# Steering_Wheel_Interface_Digital_Inputs.net
KiCad netlist of a schematic drawn in Altium Designer
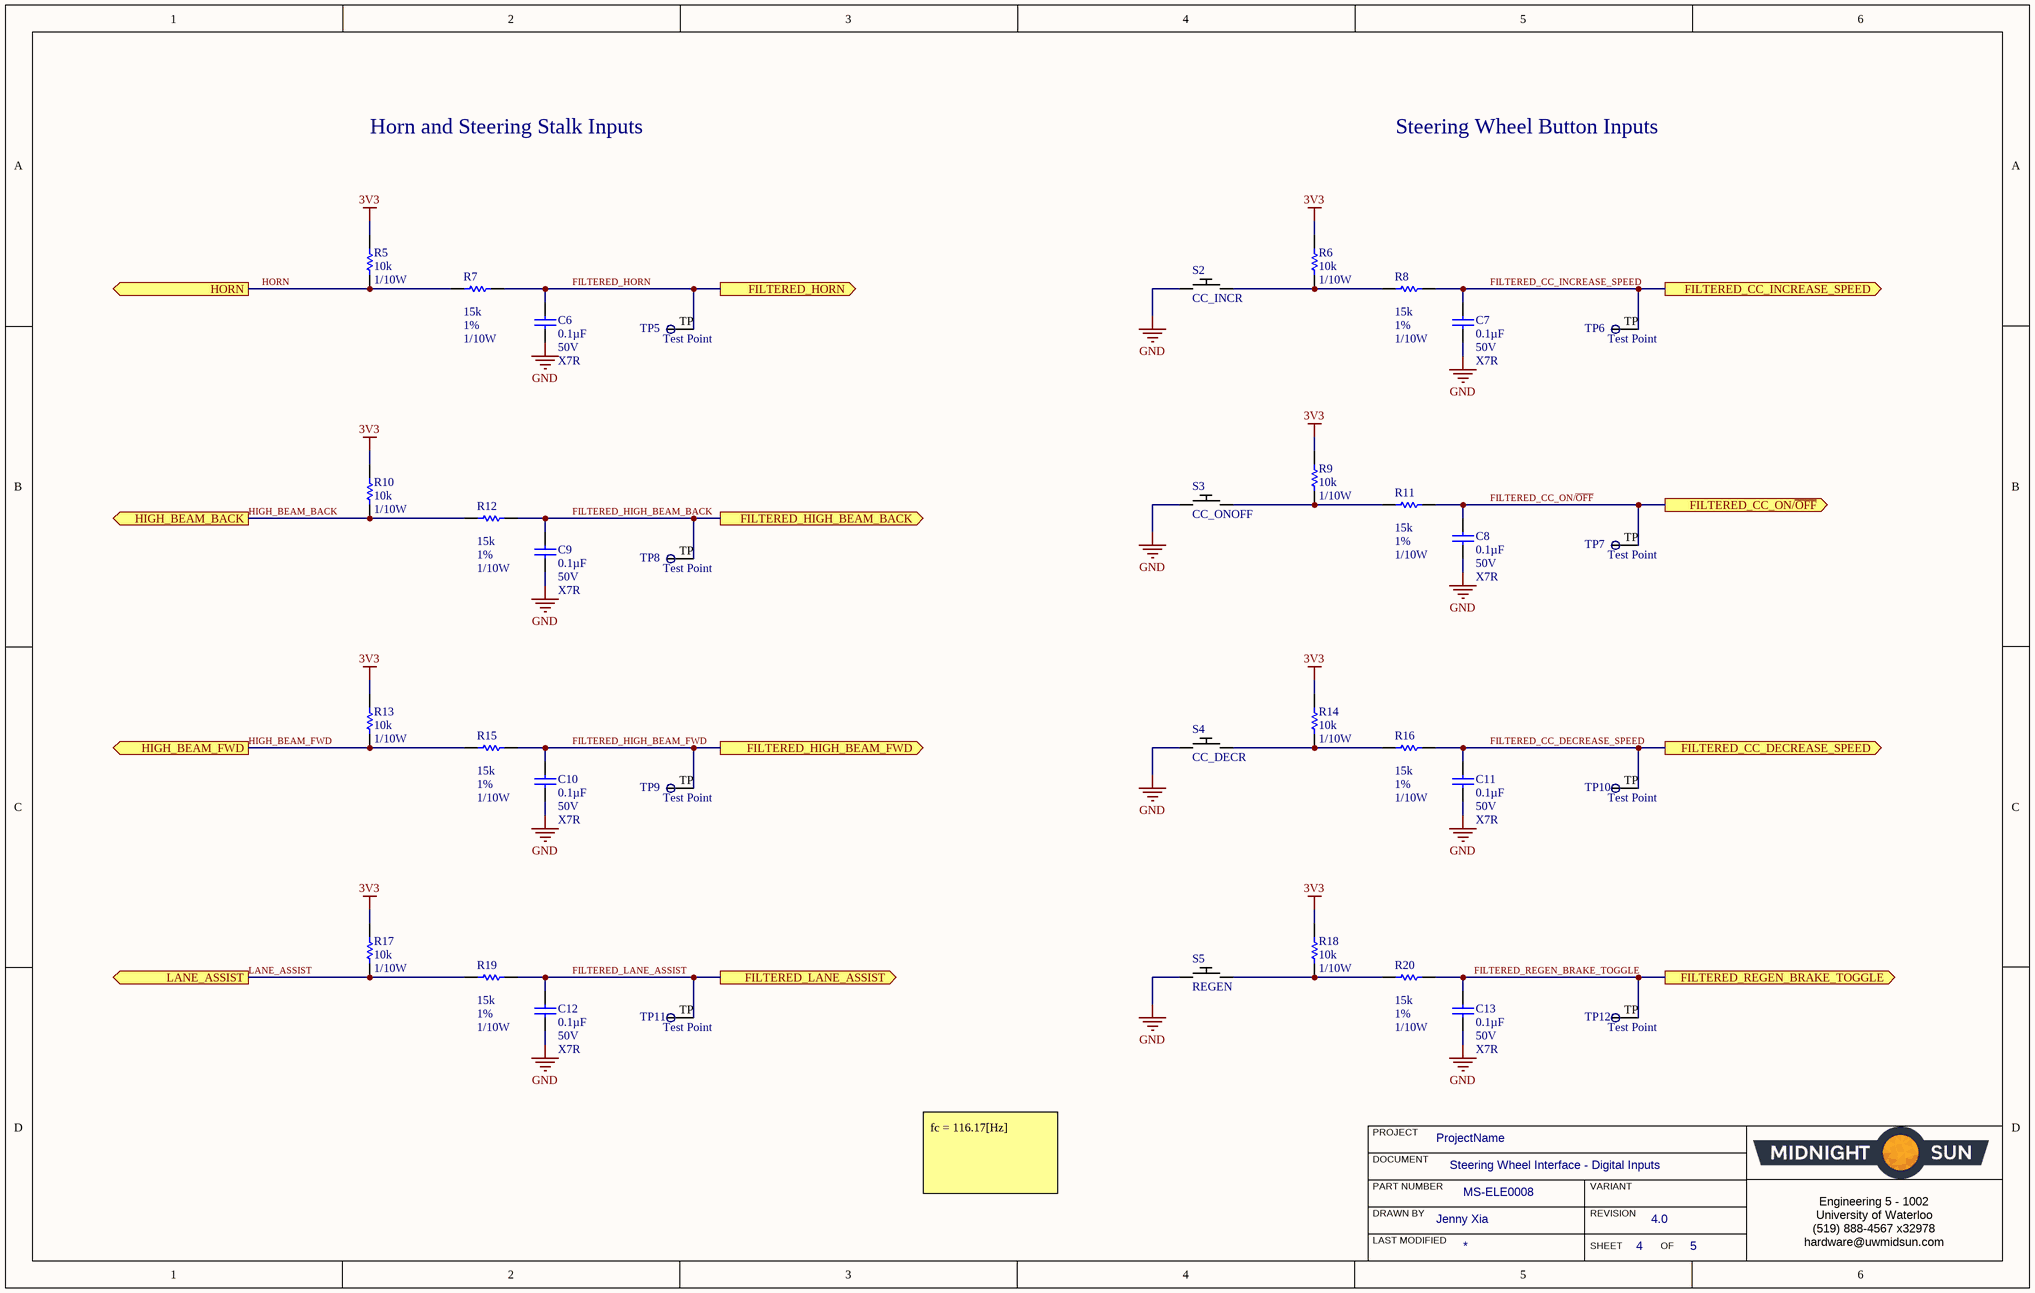
[diagram p0: Steering Wheel Interface Digital Inputs.SchDoc]

(export (version "E")
  (design (tool "Eeschema 10.0.6"))
  (components
    (comp (ref "C6")
      (value "CAP CER 0.1UF 50V 10% X7R 0603")
      (footprint "CAP, 0603")
      (description "0.10µF ±10% 50V Ceramic Capacitor X7R 0603 (1608 Metric)")
      (fields
        (field (name "TOLERANCE") "±10%")
        (field (name "CAPACITANCE") "0.1µF")
        (field (name "VOLTAGE") "50V")
        (field (name "TEMPERATURE COEFFICIENT") "X7R")
      )
      (libsource (lib "Schematic Diagrams") (part "CAP CER 0.1UF 50V 10% X7R 0603"))
    )
    (comp (ref "C7")
      (value "CAP CER 0.1UF 50V 10% X7R 0603")
      (footprint "CAP, 0603")
      (description "0.10µF ±10% 50V Ceramic Capacitor X7R 0603 (1608 Metric)")
      (fields
        (field (name "TOLERANCE") "±10%")
        (field (name "CAPACITANCE") "0.1µF")
        (field (name "VOLTAGE") "50V")
        (field (name "TEMPERATURE COEFFICIENT") "X7R")
      )
      (libsource (lib "Schematic Diagrams") (part "CAP CER 0.1UF 50V 10% X7R 0603"))
    )
    (comp (ref "C8")
      (value "CAP CER 0.1UF 50V 10% X7R 0603")
      (footprint "CAP, 0603")
      (description "0.10µF ±10% 50V Ceramic Capacitor X7R 0603 (1608 Metric)")
      (fields
        (field (name "TOLERANCE") "±10%")
        (field (name "CAPACITANCE") "0.1µF")
        (field (name "VOLTAGE") "50V")
        (field (name "TEMPERATURE COEFFICIENT") "X7R")
      )
      (libsource (lib "Schematic Diagrams") (part "CAP CER 0.1UF 50V 10% X7R 0603"))
    )
    (comp (ref "C9")
      (value "CAP CER 0.1UF 50V 10% X7R 0603")
      (footprint "CAP, 0603")
      (description "0.10µF ±10% 50V Ceramic Capacitor X7R 0603 (1608 Metric)")
      (fields
        (field (name "TOLERANCE") "±10%")
        (field (name "CAPACITANCE") "0.1µF")
        (field (name "VOLTAGE") "50V")
        (field (name "TEMPERATURE COEFFICIENT") "X7R")
      )
      (libsource (lib "Schematic Diagrams") (part "CAP CER 0.1UF 50V 10% X7R 0603"))
    )
    (comp (ref "C10")
      (value "CAP CER 0.1UF 50V 10% X7R 0603")
      (footprint "CAP, 0603")
      (description "0.10µF ±10% 50V Ceramic Capacitor X7R 0603 (1608 Metric)")
      (fields
        (field (name "TOLERANCE") "±10%")
        (field (name "CAPACITANCE") "0.1µF")
        (field (name "VOLTAGE") "50V")
        (field (name "TEMPERATURE COEFFICIENT") "X7R")
      )
      (libsource (lib "Schematic Diagrams") (part "CAP CER 0.1UF 50V 10% X7R 0603"))
    )
    (comp (ref "C11")
      (value "CAP CER 0.1UF 50V 10% X7R 0603")
      (footprint "CAP, 0603")
      (description "0.10µF ±10% 50V Ceramic Capacitor X7R 0603 (1608 Metric)")
      (fields
        (field (name "TOLERANCE") "±10%")
        (field (name "CAPACITANCE") "0.1µF")
        (field (name "VOLTAGE") "50V")
        (field (name "TEMPERATURE COEFFICIENT") "X7R")
      )
      (libsource (lib "Schematic Diagrams") (part "CAP CER 0.1UF 50V 10% X7R 0603"))
    )
    (comp (ref "C12")
      (value "CAP CER 0.1UF 50V 10% X7R 0603")
      (footprint "CAP, 0603")
      (description "0.10µF ±10% 50V Ceramic Capacitor X7R 0603 (1608 Metric)")
      (fields
        (field (name "TOLERANCE") "±10%")
        (field (name "CAPACITANCE") "0.1µF")
        (field (name "VOLTAGE") "50V")
        (field (name "TEMPERATURE COEFFICIENT") "X7R")
      )
      (libsource (lib "Schematic Diagrams") (part "CAP CER 0.1UF 50V 10% X7R 0603"))
    )
    (comp (ref "C13")
      (value "CAP CER 0.1UF 50V 10% X7R 0603")
      (footprint "CAP, 0603")
      (description "0.10µF ±10% 50V Ceramic Capacitor X7R 0603 (1608 Metric)")
      (fields
        (field (name "TOLERANCE") "±10%")
        (field (name "CAPACITANCE") "0.1µF")
        (field (name "VOLTAGE") "50V")
        (field (name "TEMPERATURE COEFFICIENT") "X7R")
      )
      (libsource (lib "Schematic Diagrams") (part "CAP CER 0.1UF 50V 10% X7R 0603"))
    )
    (comp (ref "R5")
      (value "RES 10K OHM 1% 1/10W 0603")
      (footprint "RES, 0603")
      (description "RES SMD 10K OHM 1% 1/10W 0603")
      (fields
        (field (name "TOLERANCE") "±1%")
        (field (name "RESISTANCE") "10k")
        (field (name "POWER") "1/10W")
      )
      (libsource (lib "Schematic Diagrams") (part "RES 10K OHM 1% 1/10W 0603"))
    )
    (comp (ref "R6")
      (value "RES 10K OHM 1% 1/10W 0603")
      (footprint "RES, 0603")
      (description "RES SMD 10K OHM 1% 1/10W 0603")
      (fields
        (field (name "TOLERANCE") "±1%")
        (field (name "RESISTANCE") "10k")
        (field (name "POWER") "1/10W")
      )
      (libsource (lib "Schematic Diagrams") (part "RES 10K OHM 1% 1/10W 0603"))
    )
    (comp (ref "R7")
      (value "RES SMD 15K OHM 1% 1/10W 0603")
      (footprint "RES, 0603")
      (description "15 kOhms ±1% 0.1W, 1/10W Chip Resistor 0603 (1608 Metric) Moisture Resistant Thick Film")
      (fields
        (field (name "RESISTANCE") "15k")
        (field (name "TOLERANCE") "1%")
        (field (name "MAX POWER DISSIPATION") "1/10W")
        (field (name "MANUFACTURER") "Yageo")
        (field (name "MANUFACTURER PART NUMBER") "RC0603FR-0715KL")
      )
      (libsource (lib "Schematic Diagrams") (part "RES SMD 15K OHM 1% 1/10W 0603"))
    )
    (comp (ref "R8")
      (value "RES SMD 15K OHM 1% 1/10W 0603")
      (footprint "RES, 0603")
      (description "15 kOhms ±1% 0.1W, 1/10W Chip Resistor 0603 (1608 Metric) Moisture Resistant Thick Film")
      (fields
        (field (name "RESISTANCE") "15k")
        (field (name "TOLERANCE") "1%")
        (field (name "MAX POWER DISSIPATION") "1/10W")
        (field (name "MANUFACTURER") "Yageo")
        (field (name "MANUFACTURER PART NUMBER") "RC0603FR-0715KL")
      )
      (libsource (lib "Schematic Diagrams") (part "RES SMD 15K OHM 1% 1/10W 0603"))
    )
    (comp (ref "R9")
      (value "RES 10K OHM 1% 1/10W 0603")
      (footprint "RES, 0603")
      (description "RES SMD 10K OHM 1% 1/10W 0603")
      (fields
        (field (name "TOLERANCE") "±1%")
        (field (name "RESISTANCE") "10k")
        (field (name "POWER") "1/10W")
      )
      (libsource (lib "Schematic Diagrams") (part "RES 10K OHM 1% 1/10W 0603"))
    )
    (comp (ref "R10")
      (value "RES 10K OHM 1% 1/10W 0603")
      (footprint "RES, 0603")
      (description "RES SMD 10K OHM 1% 1/10W 0603")
      (fields
        (field (name "TOLERANCE") "±1%")
        (field (name "RESISTANCE") "10k")
        (field (name "POWER") "1/10W")
      )
      (libsource (lib "Schematic Diagrams") (part "RES 10K OHM 1% 1/10W 0603"))
    )
    (comp (ref "R11")
      (value "RES SMD 15K OHM 1% 1/10W 0603")
      (footprint "RES, 0603")
      (description "15 kOhms ±1% 0.1W, 1/10W Chip Resistor 0603 (1608 Metric) Moisture Resistant Thick Film")
      (fields
        (field (name "RESISTANCE") "15k")
        (field (name "TOLERANCE") "1%")
        (field (name "MAX POWER DISSIPATION") "1/10W")
        (field (name "MANUFACTURER") "Yageo")
        (field (name "MANUFACTURER PART NUMBER") "RC0603FR-0715KL")
      )
      (libsource (lib "Schematic Diagrams") (part "RES SMD 15K OHM 1% 1/10W 0603"))
    )
    (comp (ref "R12")
      (value "RES SMD 15K OHM 1% 1/10W 0603")
      (footprint "RES, 0603")
      (description "15 kOhms ±1% 0.1W, 1/10W Chip Resistor 0603 (1608 Metric) Moisture Resistant Thick Film")
      (fields
        (field (name "RESISTANCE") "15k")
        (field (name "TOLERANCE") "1%")
        (field (name "MAX POWER DISSIPATION") "1/10W")
        (field (name "MANUFACTURER") "Yageo")
        (field (name "MANUFACTURER PART NUMBER") "RC0603FR-0715KL")
      )
      (libsource (lib "Schematic Diagrams") (part "RES SMD 15K OHM 1% 1/10W 0603"))
    )
    (comp (ref "R13")
      (value "RES 10K OHM 1% 1/10W 0603")
      (footprint "RES, 0603")
      (description "RES SMD 10K OHM 1% 1/10W 0603")
      (fields
        (field (name "TOLERANCE") "±1%")
        (field (name "RESISTANCE") "10k")
        (field (name "POWER") "1/10W")
      )
      (libsource (lib "Schematic Diagrams") (part "RES 10K OHM 1% 1/10W 0603"))
    )
    (comp (ref "R14")
      (value "RES 10K OHM 1% 1/10W 0603")
      (footprint "RES, 0603")
      (description "RES SMD 10K OHM 1% 1/10W 0603")
      (fields
        (field (name "TOLERANCE") "±1%")
        (field (name "RESISTANCE") "10k")
        (field (name "POWER") "1/10W")
      )
      (libsource (lib "Schematic Diagrams") (part "RES 10K OHM 1% 1/10W 0603"))
    )
    (comp (ref "R15")
      (value "RES SMD 15K OHM 1% 1/10W 0603")
      (footprint "RES, 0603")
      (description "15 kOhms ±1% 0.1W, 1/10W Chip Resistor 0603 (1608 Metric) Moisture Resistant Thick Film")
      (fields
        (field (name "RESISTANCE") "15k")
        (field (name "TOLERANCE") "1%")
        (field (name "MAX POWER DISSIPATION") "1/10W")
        (field (name "MANUFACTURER") "Yageo")
        (field (name "MANUFACTURER PART NUMBER") "RC0603FR-0715KL")
      )
      (libsource (lib "Schematic Diagrams") (part "RES SMD 15K OHM 1% 1/10W 0603"))
    )
    (comp (ref "R16")
      (value "RES SMD 15K OHM 1% 1/10W 0603")
      (footprint "RES, 0603")
      (description "15 kOhms ±1% 0.1W, 1/10W Chip Resistor 0603 (1608 Metric) Moisture Resistant Thick Film")
      (fields
        (field (name "RESISTANCE") "15k")
        (field (name "TOLERANCE") "1%")
        (field (name "MAX POWER DISSIPATION") "1/10W")
        (field (name "MANUFACTURER") "Yageo")
        (field (name "MANUFACTURER PART NUMBER") "RC0603FR-0715KL")
      )
      (libsource (lib "Schematic Diagrams") (part "RES SMD 15K OHM 1% 1/10W 0603"))
    )
    (comp (ref "R17")
      (value "RES 10K OHM 1% 1/10W 0603")
      (footprint "RES, 0603")
      (description "RES SMD 10K OHM 1% 1/10W 0603")
      (fields
        (field (name "TOLERANCE") "±1%")
        (field (name "RESISTANCE") "10k")
        (field (name "POWER") "1/10W")
      )
      (libsource (lib "Schematic Diagrams") (part "RES 10K OHM 1% 1/10W 0603"))
    )
    (comp (ref "R18")
      (value "RES 10K OHM 1% 1/10W 0603")
      (footprint "RES, 0603")
      (description "RES SMD 10K OHM 1% 1/10W 0603")
      (fields
        (field (name "TOLERANCE") "±1%")
        (field (name "RESISTANCE") "10k")
        (field (name "POWER") "1/10W")
      )
      (libsource (lib "Schematic Diagrams") (part "RES 10K OHM 1% 1/10W 0603"))
    )
    (comp (ref "R19")
      (value "RES SMD 15K OHM 1% 1/10W 0603")
      (footprint "RES, 0603")
      (description "15 kOhms ±1% 0.1W, 1/10W Chip Resistor 0603 (1608 Metric) Moisture Resistant Thick Film")
      (fields
        (field (name "RESISTANCE") "15k")
        (field (name "TOLERANCE") "1%")
        (field (name "MAX POWER DISSIPATION") "1/10W")
        (field (name "MANUFACTURER") "Yageo")
        (field (name "MANUFACTURER PART NUMBER") "RC0603FR-0715KL")
      )
      (libsource (lib "Schematic Diagrams") (part "RES SMD 15K OHM 1% 1/10W 0603"))
    )
    (comp (ref "R20")
      (value "RES SMD 15K OHM 1% 1/10W 0603")
      (footprint "RES, 0603")
      (description "15 kOhms ±1% 0.1W, 1/10W Chip Resistor 0603 (1608 Metric) Moisture Resistant Thick Film")
      (fields
        (field (name "RESISTANCE") "15k")
        (field (name "TOLERANCE") "1%")
        (field (name "MAX POWER DISSIPATION") "1/10W")
        (field (name "MANUFACTURER") "Yageo")
        (field (name "MANUFACTURER PART NUMBER") "RC0603FR-0715KL")
      )
      (libsource (lib "Schematic Diagrams") (part "RES SMD 15K OHM 1% 1/10W 0603"))
    )
    (comp (ref "S2")
      (value "CC_INCR")
      (footprint "SW SPST-NO ESE-20C321")
      (description "Pushbutton Switch SPST-NO Standard Through Hole")
      (fields (field (name "MANUFACTURER") "Panasonic") (field (name "MANUFACTURER PART NUMBER") "ESE20C321"))
      (libsource (lib "Schematic Diagrams") (part "SW PUSH SPST-NO 0.1A 14V"))
    )
    (comp (ref "S3")
      (value "CC_ONOFF")
      (footprint "SW SPST-NO ESE-20C321")
      (description "Pushbutton Switch SPST-NO Standard Through Hole")
      (fields (field (name "MANUFACTURER") "Panasonic") (field (name "MANUFACTURER PART NUMBER") "ESE20C321"))
      (libsource (lib "Schematic Diagrams") (part "SW PUSH SPST-NO 0.1A 14V"))
    )
    (comp (ref "S4")
      (value "CC_DECR")
      (footprint "SW SPST-NO ESE-20C321")
      (description "Pushbutton Switch SPST-NO Standard Through Hole")
      (fields (field (name "MANUFACTURER") "Panasonic") (field (name "MANUFACTURER PART NUMBER") "ESE20C321"))
      (libsource (lib "Schematic Diagrams") (part "SW PUSH SPST-NO 0.1A 14V"))
    )
    (comp (ref "S5")
      (value "REGEN")
      (footprint "SW SPST-NO ESE-20C321")
      (description "Pushbutton Switch SPST-NO Standard Through Hole")
      (fields (field (name "MANUFACTURER") "Panasonic") (field (name "MANUFACTURER PART NUMBER") "ESE20C321"))
      (libsource (lib "Schematic Diagrams") (part "SW PUSH SPST-NO 0.1A 14V"))
    )
    (comp (ref "TP5")
      (value "Test Point")
      (footprint "Test Point")
      (libsource (lib "Schematic Diagrams") (part "Test Point"))
    )
    (comp (ref "TP6")
      (value "Test Point")
      (footprint "Test Point")
      (libsource (lib "Schematic Diagrams") (part "Test Point"))
    )
    (comp (ref "TP7")
      (value "Test Point")
      (footprint "Test Point")
      (libsource (lib "Schematic Diagrams") (part "Test Point"))
    )
    (comp (ref "TP8")
      (value "Test Point")
      (footprint "Test Point")
      (libsource (lib "Schematic Diagrams") (part "Test Point"))
    )
    (comp (ref "TP9")
      (value "Test Point")
      (footprint "Test Point")
      (libsource (lib "Schematic Diagrams") (part "Test Point"))
    )
    (comp (ref "TP10")
      (value "Test Point")
      (footprint "Test Point")
      (libsource (lib "Schematic Diagrams") (part "Test Point"))
    )
    (comp (ref "TP11")
      (value "Test Point")
      (footprint "Test Point")
      (libsource (lib "Schematic Diagrams") (part "Test Point"))
    )
    (comp (ref "TP12")
      (value "Test Point")
      (footprint "Test Point")
      (libsource (lib "Schematic Diagrams") (part "Test Point"))
    )
  )
  (nets
    (net (code "1") (name "/FILTERED_CC_DECREASE_SPEED") (class "Default")
      (node (ref "C11") (pin "1") (pinfunction "1_1") (pintype "passive"))
      (node (ref "R16") (pin "1") (pinfunction "1_1") (pintype "passive"))
      (node (ref "TP10") (pin "TP") (pinfunction "1_TP") (pintype "passive"))
    )
    (net (code "2") (name "/FILTERED_CC_INCREASE_SPEED") (class "Default")
      (node (ref "C7") (pin "1") (pinfunction "1_1") (pintype "passive"))
      (node (ref "R8") (pin "1") (pinfunction "1_1") (pintype "passive"))
      (node (ref "TP6") (pin "TP") (pinfunction "1_TP") (pintype "passive"))
    )
    (net (code "3") (name "/FILTERED_CC_ON{slash}~{OFF}") (class "Default")
      (node (ref "C8") (pin "1") (pinfunction "1_1") (pintype "passive"))
      (node (ref "R11") (pin "1") (pinfunction "1_1") (pintype "passive"))
      (node (ref "TP7") (pin "TP") (pinfunction "1_TP") (pintype "passive"))
    )
    (net (code "4") (name "/FILTERED_HIGH_BEAM_BACK") (class "Default")
      (node (ref "C9") (pin "1") (pinfunction "1_1") (pintype "passive"))
      (node (ref "R12") (pin "1") (pinfunction "1_1") (pintype "passive"))
      (node (ref "TP8") (pin "TP") (pinfunction "1_TP") (pintype "passive"))
    )
    (net (code "5") (name "/FILTERED_HIGH_BEAM_FWD") (class "Default")
      (node (ref "C10") (pin "1") (pinfunction "1_1") (pintype "passive"))
      (node (ref "R15") (pin "1") (pinfunction "1_1") (pintype "passive"))
      (node (ref "TP9") (pin "TP") (pinfunction "1_TP") (pintype "passive"))
    )
    (net (code "6") (name "/FILTERED_HORN") (class "Default")
      (node (ref "C6") (pin "1") (pinfunction "1_1") (pintype "passive"))
      (node (ref "R7") (pin "1") (pinfunction "1_1") (pintype "passive"))
      (node (ref "TP5") (pin "TP") (pinfunction "1_TP") (pintype "passive"))
    )
    (net (code "7") (name "/FILTERED_LANE_ASSIST") (class "Default")
      (node (ref "C12") (pin "1") (pinfunction "1_1") (pintype "passive"))
      (node (ref "R19") (pin "1") (pinfunction "1_1") (pintype "passive"))
      (node (ref "TP11") (pin "TP") (pinfunction "1_TP") (pintype "passive"))
    )
    (net (code "8") (name "/FILTERED_REGEN_BRAKE_TOGGLE") (class "Default")
      (node (ref "C13") (pin "1") (pinfunction "1_1") (pintype "passive"))
      (node (ref "R20") (pin "1") (pinfunction "1_1") (pintype "passive"))
      (node (ref "TP12") (pin "TP") (pinfunction "1_TP") (pintype "passive"))
    )
    (net (code "9") (name "/HIGH_BEAM_BACK") (class "Default")
      (node (ref "R10") (pin "2") (pinfunction "2_2") (pintype "passive"))
      (node (ref "R12") (pin "2") (pinfunction "2_2") (pintype "passive"))
    )
    (net (code "10") (name "/HIGH_BEAM_FWD") (class "Default")
      (node (ref "R13") (pin "2") (pinfunction "2_2") (pintype "passive"))
      (node (ref "R15") (pin "2") (pinfunction "2_2") (pintype "passive"))
    )
    (net (code "11") (name "/HORN") (class "Default")
      (node (ref "R5") (pin "2") (pinfunction "2_2") (pintype "passive"))
      (node (ref "R7") (pin "2") (pinfunction "2_2") (pintype "passive"))
    )
    (net (code "12") (name "/LANE_ASSIST") (class "Default")
      (node (ref "R17") (pin "2") (pinfunction "2_2") (pintype "passive"))
      (node (ref "R19") (pin "2") (pinfunction "2_2") (pintype "passive"))
    )
    (net (code "13") (name "3V3") (class "Default")
      (node (ref "R10") (pin "1") (pinfunction "1_1") (pintype "passive"))
      (node (ref "R13") (pin "1") (pinfunction "1_1") (pintype "passive"))
      (node (ref "R14") (pin "1") (pinfunction "1_1") (pintype "passive"))
      (node (ref "R17") (pin "1") (pinfunction "1_1") (pintype "passive"))
      (node (ref "R18") (pin "1") (pinfunction "1_1") (pintype "passive"))
      (node (ref "R5") (pin "1") (pinfunction "1_1") (pintype "passive"))
      (node (ref "R6") (pin "1") (pinfunction "1_1") (pintype "passive"))
      (node (ref "R9") (pin "1") (pinfunction "1_1") (pintype "passive"))
    )
    (net (code "14") (name "GND") (class "Default")
      (node (ref "C10") (pin "2") (pinfunction "2_2") (pintype "passive"))
      (node (ref "C11") (pin "2") (pinfunction "2_2") (pintype "passive"))
      (node (ref "C12") (pin "2") (pinfunction "2_2") (pintype "passive"))
      (node (ref "C13") (pin "2") (pinfunction "2_2") (pintype "passive"))
      (node (ref "C6") (pin "2") (pinfunction "2_2") (pintype "passive"))
      (node (ref "C7") (pin "2") (pinfunction "2_2") (pintype "passive"))
      (node (ref "C8") (pin "2") (pinfunction "2_2") (pintype "passive"))
      (node (ref "C9") (pin "2") (pinfunction "2_2") (pintype "passive"))
      (node (ref "S2") (pin "1") (pinfunction "1_1") (pintype "passive"))
      (node (ref "S3") (pin "1") (pinfunction "1_1") (pintype "passive"))
      (node (ref "S4") (pin "1") (pinfunction "1_1") (pintype "passive"))
      (node (ref "S5") (pin "1") (pinfunction "1_1") (pintype "passive"))
    )
    (net (code "15") (name "Net-(R6-Pad2)") (class "Default")
      (node (ref "R6") (pin "2") (pinfunction "2_2") (pintype "passive"))
      (node (ref "R8") (pin "2") (pinfunction "2_2") (pintype "passive"))
      (node (ref "S2") (pin "2") (pinfunction "2_2") (pintype "passive"))
    )
    (net (code "16") (name "Net-(R11-Pad2)") (class "Default")
      (node (ref "R11") (pin "2") (pinfunction "2_2") (pintype "passive"))
      (node (ref "R9") (pin "2") (pinfunction "2_2") (pintype "passive"))
      (node (ref "S3") (pin "2") (pinfunction "2_2") (pintype "passive"))
    )
    (net (code "17") (name "Net-(R14-Pad2)") (class "Default")
      (node (ref "R14") (pin "2") (pinfunction "2_2") (pintype "passive"))
      (node (ref "R16") (pin "2") (pinfunction "2_2") (pintype "passive"))
      (node (ref "S4") (pin "2") (pinfunction "2_2") (pintype "passive"))
    )
    (net (code "18") (name "Net-(R18-Pad2)") (class "Default")
      (node (ref "R18") (pin "2") (pinfunction "2_2") (pintype "passive"))
      (node (ref "R20") (pin "2") (pinfunction "2_2") (pintype "passive"))
      (node (ref "S5") (pin "2") (pinfunction "2_2") (pintype "passive"))
    )
  )
)
